# design.net
KiCad netlist of a schematic drawn in Altium Designer
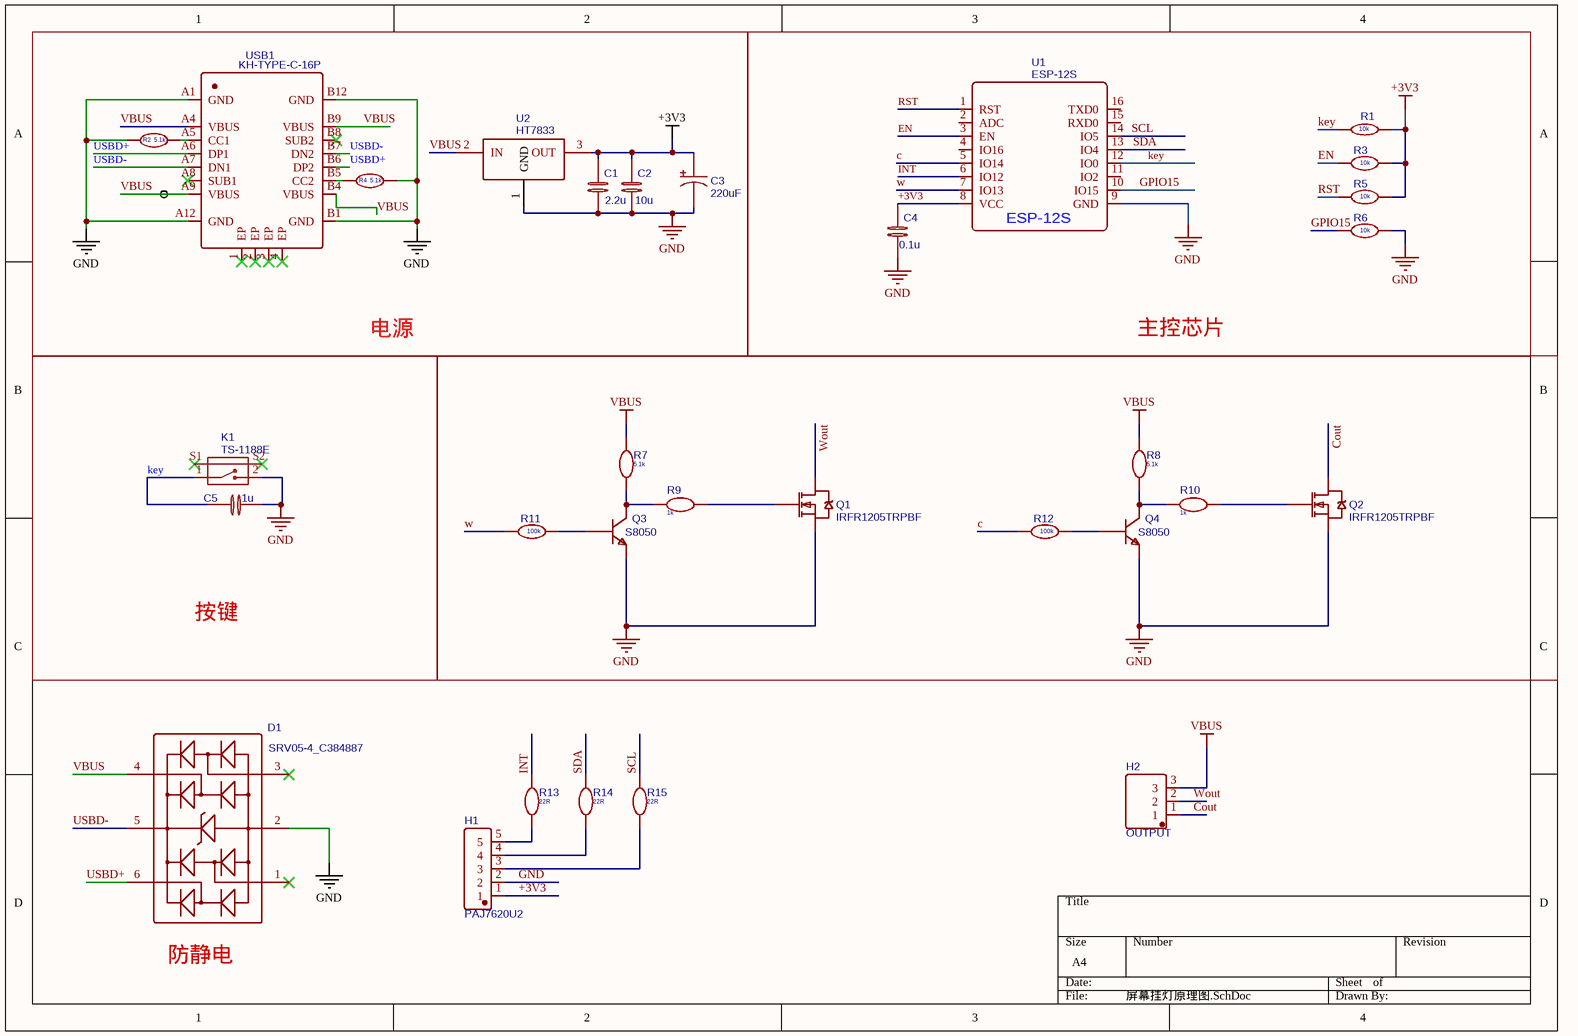
[diagram p0: 屏幕挂灯原理图.SchDoc]

(export (version "E")
  (design (tool "Eeschema 10.0.6"))
  (components
    (comp (ref "C1")
      (value "2.2u")
      (footprint "C0603")
      (fields (field (name "CONTRIBUTOR") "LCEDA_Lib"))
      (libsource (lib "altium-import") (part "root_1_2.2u_"))
    )
    (comp (ref "C2")
      (value "10u")
      (footprint "C0603")
      (fields (field (name "CONTRIBUTOR") "LCEDA_Lib"))
      (libsource (lib "altium-import") (part "root_1_10u_"))
    )
    (comp (ref "C3")
      (value "220uF")
      (footprint "CAP-SMD_BD5.0-L5.3-W5.3-FD")
      (fields
        (field (name "BOM_SUPPLIER PART") "C336271")
        (field (name "BOM_MANUFACTURER PART") "EEEFT0J221AR")
        (field (name "CONTRIBUTOR") "LCSC")
      )
      (libsource (lib "altium-import") (part "root_0_220uF_"))
    )
    (comp (ref "C4")
      (value "0.1u")
      (footprint "C0603")
      (fields (field (name "CONTRIBUTOR") "LCEDA_Lib"))
      (libsource (lib "altium-import") (part "root_1_0.1u_"))
    )
    (comp (ref "C5")
      (value "1u")
      (footprint "C0603")
      (fields (field (name "CONTRIBUTOR") "LCEDA_Lib"))
      (libsource (lib "altium-import") (part "root_2_1u_"))
    )
    (comp (ref "D1")
      (value "SRV05-4_C384887")
      (footprint "SOT-23-6_L2.9-W1.6-P0.95-LS2.8-BR")
      (fields
        (field (name "BOM_SUPPLIER PART") "C384887")
        (field (name "BOM_MANUFACTURER PART") "SRV05-4")
        (field (name "CONTRIBUTOR") "LCSC")
      )
      (libsource (lib "altium-import") (part "root_1_SRV05-4_C384887_"))
    )
    (comp (ref "H1")
      (value "PAJ7620U2")
      (footprint "HDR-TH_5P-P2.54-V-M")
      (fields
        (field (name "BOM_SUPPLIER PART") "C2932699")
        (field (name "BOM_MANUFACTURER PART") "KH-2.54PH180-1X5P-L11.5")
        (field (name "CONTRIBUTOR") "LCSC")
      )
      (libsource (lib "altium-import") (part "root_2_KH-2.54PH180-1X5P-L11.5_"))
    )
    (comp (ref "H2")
      (value "OUTPUT")
      (footprint "HDR-TH_3P-P2.54-V-M-1")
      (fields
        (field (name "BOM_SUPPLIER PART") "C168677")
        (field (name "BOM_MANUFACTURER PART") "68000-103HLF")
        (field (name "CONTRIBUTOR") "LCSC")
      )
      (libsource (lib "altium-import") (part "root_2_68000-103HLF_"))
    )
    (comp (ref "K1")
      (value "TS-1188E")
      (footprint "SMD SWITCH 7X3.6X2.7")
      (fields
        (field (name "BOM_MANUFACTURER PART") "3*6*3.5 Side press  High temperature")
        (field (name "BOM_SUPPLIER PART") "C37327")
      )
      (libsource (lib "altium-import") (part "root_0_TS-1188E_"))
    )
    (comp (ref "Q1")
      (value "IRFR1205TRPBF")
      (footprint "TO-252-2_L6.5-W6.1-P4.58-LS10.0-TR")
      (fields (field (name "BOM_SUPPLIER PART") "C81467"))
      (libsource (lib "altium-import") (part "root_0_IRFR1205TRPBF_"))
    )
    (comp (ref "Q2")
      (value "IRFR1205TRPBF")
      (footprint "TO-252-2_L6.5-W6.1-P4.58-LS10.0-TR")
      (fields (field (name "BOM_SUPPLIER PART") "C81467"))
      (libsource (lib "altium-import") (part "root_0_IRFR1205TRPBF_"))
    )
    (comp (ref "Q3")
      (value "S8050")
      (footprint "SOT-23(SOT-23-3)")
      (fields (field (name "BOM_SUPPLIER PART") "C139514") (field (name "CONTRIBUTOR") "LCSC"))
      (libsource (lib "altium-import") (part "root_2_S8050_"))
    )
    (comp (ref "Q4")
      (value "S8050")
      (footprint "SOT-23(SOT-23-3)")
      (fields (field (name "BOM_SUPPLIER PART") "C139514") (field (name "CONTRIBUTOR") "LCSC"))
      (libsource (lib "altium-import") (part "root_2_S8050_"))
    )
    (comp (ref "R1")
      (value "10k")
      (footprint "R0603")
      (fields
        (field (name "BOM_MANUFACTURER PART") "CRCW060310K0JNEA")
        (field (name "BOM_SUPPLIER PART") "C169103")
      )
      (libsource (lib "altium-import") (part "root_0_10k_"))
    )
    (comp (ref "R2")
      (value "5.1k")
      (footprint "R0603")
      (fields (field (name "CONTRIBUTOR") "LCEDA_Lib"))
      (libsource (lib "altium-import") (part "root_0_5.1k_"))
    )
    (comp (ref "R3")
      (value "10k")
      (footprint "R0603")
      (fields (field (name "CONTRIBUTOR") "LCEDA_Lib"))
      (libsource (lib "altium-import") (part "root_0_NC_"))
    )
    (comp (ref "R4")
      (value "5.1k")
      (footprint "R0603")
      (fields (field (name "CONTRIBUTOR") "LCEDA_Lib"))
      (libsource (lib "altium-import") (part "root_0_5.1k_"))
    )
    (comp (ref "R5")
      (value "10k")
      (footprint "R0603")
      (fields (field (name "CONTRIBUTOR") "LCEDA_Lib"))
      (libsource (lib "altium-import") (part "root_0_NC_"))
    )
    (comp (ref "R6")
      (value "10k")
      (footprint "R0603")
      (fields (field (name "CONTRIBUTOR") "LCEDA_Lib"))
      (libsource (lib "altium-import") (part "root_0_NC_"))
    )
    (comp (ref "R7")
      (value "5.1k")
      (footprint "R0603")
      (fields (field (name "CONTRIBUTOR") "LCEDA_Lib"))
      (libsource (lib "altium-import") (part "root_1_NC_"))
    )
    (comp (ref "R8")
      (value "5.1k")
      (footprint "R0603")
      (fields (field (name "CONTRIBUTOR") "LCEDA_Lib"))
      (libsource (lib "altium-import") (part "root_1_NC_"))
    )
    (comp (ref "R9")
      (value "1k")
      (footprint "R0603")
      (fields (field (name "CONTRIBUTOR") "LCEDA_Lib"))
      (libsource (lib "altium-import") (part "root_2_NC_"))
    )
    (comp (ref "R10")
      (value "1k")
      (footprint "R0603")
      (fields (field (name "CONTRIBUTOR") "LCEDA_Lib"))
      (libsource (lib "altium-import") (part "root_2_NC_"))
    )
    (comp (ref "R11")
      (value "100k")
      (footprint "R0603")
      (fields (field (name "CONTRIBUTOR") "LCEDA_Lib"))
      (libsource (lib "altium-import") (part "root_0_NC_"))
    )
    (comp (ref "R12")
      (value "100k")
      (footprint "R0603")
      (fields (field (name "CONTRIBUTOR") "LCEDA_Lib"))
      (libsource (lib "altium-import") (part "root_0_NC_"))
    )
    (comp (ref "R13")
      (value "22R")
      (footprint "R0603")
      (fields (field (name "CONTRIBUTOR") "LCEDA_Lib"))
      (libsource (lib "altium-import") (part "root_1_NC_"))
    )
    (comp (ref "R14")
      (value "22R")
      (footprint "R0603")
      (fields (field (name "CONTRIBUTOR") "LCEDA_Lib"))
      (libsource (lib "altium-import") (part "root_1_NC_"))
    )
    (comp (ref "R15")
      (value "22R")
      (footprint "R0603")
      (fields (field (name "CONTRIBUTOR") "LCEDA_Lib"))
      (libsource (lib "altium-import") (part "root_1_NC_"))
    )
    (comp (ref "U1")
      (value "ESP-12S")
      (footprint "WIFIM-SMD_ESP-12F-ESP8266MOD")
      (fields (field (name "BOM_SUPPLIER PART") "C82898") (field (name "CONTRIBUTOR") "HalfSweet"))
      (libsource (lib "altium-import") (part "root_0_ESP-12S_"))
    )
    (comp (ref "U2")
      (value "HT7833")
      (footprint "SOT-89_L4.5-W2.5-P1.50-LS4.2-BR")
      (fields (field (name "BOM_SUPPLIER PART") "C50936"))
      (libsource (lib "altium-import") (part "root_0_HT7833_"))
    )
    (comp (ref "USB1")
      (value "KH-TYPE-C-16P")
      (footprint "PcbLib1screen:USB-C-SMD_KH-TYPE-C-16P")
      (fields (field (name "BOM_SUPPLIER PART") "C709357") (field (name "CONTRIBUTOR") "LCSC"))
      (libsource (lib "altium-import") (part "root_0_KH-TYPE-C-16P_"))
    )
  )
  (nets
    (net (code "1") (name "+3V3") (class "Default")
      (node (ref "C1") (pin "2") (pinfunction "2_2") (pintype "passive"))
      (node (ref "C2") (pin "2") (pinfunction "2_2") (pintype "passive"))
      (node (ref "C3") (pin "1") (pinfunction "1_1") (pintype "passive"))
      (node (ref "C4") (pin "2") (pinfunction "2_2") (pintype "passive"))
      (node (ref "H1") (pin "1") (pinfunction "1_1") (pintype "passive"))
      (node (ref "R1") (pin "1") (pinfunction "1_1") (pintype "passive"))
      (node (ref "R3") (pin "2") (pinfunction "2_2") (pintype "passive"))
      (node (ref "R5") (pin "2") (pinfunction "2_2") (pintype "passive"))
      (node (ref "U1") (pin "8") (pinfunction "VCC_8") (pintype "passive"))
      (node (ref "U2") (pin "3") (pinfunction "OUT_3") (pintype "passive"))
    )
    (net (code "2") (name "/Cout") (class "Default")
      (node (ref "H2") (pin "1") (pinfunction "1_1") (pintype "passive"))
      (node (ref "Q2") (pin "4") (pinfunction "D_4") (pintype "passive"))
    )
    (net (code "3") (name "/EN") (class "Default")
      (node (ref "R3") (pin "1") (pinfunction "1_1") (pintype "passive"))
      (node (ref "U1") (pin "3") (pinfunction "EN_3") (pintype "passive"))
    )
    (net (code "4") (name "/GPIO15") (class "Default")
      (node (ref "R6") (pin "1") (pinfunction "1_1") (pintype "passive"))
      (node (ref "U1") (pin "10") (pinfunction "IO15_10") (pintype "passive"))
    )
    (net (code "5") (name "/INT") (class "Default")
      (node (ref "R13") (pin "2") (pinfunction "2_2") (pintype "passive"))
      (node (ref "U1") (pin "6") (pinfunction "IO12_6") (pintype "passive"))
    )
    (net (code "6") (name "/RST") (class "Default")
      (node (ref "R5") (pin "1") (pinfunction "1_1") (pintype "passive"))
      (node (ref "U1") (pin "1") (pinfunction "RST_1") (pintype "passive"))
    )
    (net (code "7") (name "/SCL") (class "Default")
      (node (ref "R15") (pin "2") (pinfunction "2_2") (pintype "passive"))
      (node (ref "U1") (pin "14") (pinfunction "IO5_14") (pintype "passive"))
    )
    (net (code "8") (name "/SDA") (class "Default")
      (node (ref "R14") (pin "2") (pinfunction "2_2") (pintype "passive"))
      (node (ref "U1") (pin "13") (pinfunction "IO4_13") (pintype "passive"))
    )
    (net (code "9") (name "/USBD+") (class "Default")
      (node (ref "D1") (pin "6") (pinfunction "IO2_6") (pintype "passive"))
      (node (ref "USB1") (pin "A6") (pinfunction "DP1_A6") (pintype "passive"))
      (node (ref "USB1") (pin "B6") (pinfunction "DP2_B6") (pintype "passive"))
    )
    (net (code "10") (name "/USBD-") (class "Default")
      (node (ref "D1") (pin "5") (pinfunction "VCC_5") (pintype "passive"))
      (node (ref "USB1") (pin "A7") (pinfunction "DN1_A7") (pintype "passive"))
      (node (ref "USB1") (pin "B7") (pinfunction "DN2_B7") (pintype "passive"))
    )
    (net (code "11") (name "/Wout") (class "Default")
      (node (ref "H2") (pin "2") (pinfunction "2_2") (pintype "passive"))
      (node (ref "Q1") (pin "4") (pinfunction "D_4") (pintype "passive"))
    )
    (net (code "12") (name "/c") (class "Default")
      (node (ref "R12") (pin "1") (pinfunction "1_1") (pintype "passive"))
      (node (ref "U1") (pin "5") (pinfunction "IO14_5") (pintype "passive"))
    )
    (net (code "13") (name "/key") (class "Default")
      (node (ref "C5") (pin "2") (pinfunction "2_2") (pintype "passive"))
      (node (ref "K1") (pin "1") (pinfunction "1_1") (pintype "passive"))
      (node (ref "R1") (pin "2") (pinfunction "2_2") (pintype "passive"))
      (node (ref "U1") (pin "12") (pinfunction "IO0_12") (pintype "passive"))
    )
    (net (code "14") (name "/w") (class "Default")
      (node (ref "R11") (pin "1") (pinfunction "1_1") (pintype "passive"))
      (node (ref "U1") (pin "7") (pinfunction "IO13_7") (pintype "passive"))
    )
    (net (code "15") (name "GND") (class "Default")
      (node (ref "C1") (pin "1") (pinfunction "1_1") (pintype "passive"))
      (node (ref "C2") (pin "1") (pinfunction "1_1") (pintype "passive"))
      (node (ref "C3") (pin "2") (pinfunction "2_2") (pintype "passive"))
      (node (ref "C4") (pin "1") (pinfunction "1_1") (pintype "passive"))
      (node (ref "C5") (pin "1") (pinfunction "1_1") (pintype "passive"))
      (node (ref "D1") (pin "2") (pinfunction "GND_2") (pintype "passive"))
      (node (ref "H1") (pin "2") (pinfunction "2_2") (pintype "passive"))
      (node (ref "K1") (pin "2") (pinfunction "2_2") (pintype "passive"))
      (node (ref "Q1") (pin "3") (pinfunction "S_3") (pintype "passive"))
      (node (ref "Q2") (pin "3") (pinfunction "S_3") (pintype "passive"))
      (node (ref "Q3") (pin "2") (pinfunction "E_2") (pintype "passive"))
      (node (ref "Q4") (pin "2") (pinfunction "E_2") (pintype "passive"))
      (node (ref "R2") (pin "1") (pinfunction "1_1") (pintype "passive"))
      (node (ref "R4") (pin "2") (pinfunction "2_2") (pintype "passive"))
      (node (ref "R6") (pin "2") (pinfunction "2_2") (pintype "passive"))
      (node (ref "U1") (pin "9") (pinfunction "GND_9") (pintype "passive"))
      (node (ref "U2") (pin "1") (pinfunction "GND_1") (pintype "passive"))
      (node (ref "USB1") (pin "A1") (pinfunction "GND_A1") (pintype "passive"))
      (node (ref "USB1") (pin "A12") (pinfunction "GND_A12") (pintype "passive"))
      (node (ref "USB1") (pin "B1") (pinfunction "GND_B1") (pintype "passive"))
      (node (ref "USB1") (pin "B12") (pinfunction "GND_B12") (pintype "passive"))
    )
    (net (code "16") (name "Net-(H1-Pad3)") (class "Default")
      (node (ref "H1") (pin "3") (pinfunction "3_3") (pintype "passive"))
      (node (ref "R15") (pin "1") (pinfunction "1_1") (pintype "passive"))
    )
    (net (code "17") (name "Net-(H1-Pad4)") (class "Default")
      (node (ref "H1") (pin "4") (pinfunction "4_4") (pintype "passive"))
      (node (ref "R14") (pin "1") (pinfunction "1_1") (pintype "passive"))
    )
    (net (code "18") (name "Net-(H1-Pad5)") (class "Default")
      (node (ref "H1") (pin "5") (pinfunction "5_5") (pintype "passive"))
      (node (ref "R13") (pin "1") (pinfunction "1_1") (pintype "passive"))
    )
    (net (code "19") (name "Net-(Q1-G)") (class "Default")
      (node (ref "Q1") (pin "1") (pinfunction "G_1") (pintype "passive"))
      (node (ref "R9") (pin "1") (pinfunction "1_1") (pintype "passive"))
    )
    (net (code "20") (name "Net-(Q2-G)") (class "Default")
      (node (ref "Q2") (pin "1") (pinfunction "G_1") (pintype "passive"))
      (node (ref "R10") (pin "1") (pinfunction "1_1") (pintype "passive"))
    )
    (net (code "21") (name "Net-(Q3-B)") (class "Default")
      (node (ref "Q3") (pin "1") (pinfunction "B_1") (pintype "passive"))
      (node (ref "R11") (pin "2") (pinfunction "2_2") (pintype "passive"))
    )
    (net (code "22") (name "Net-(Q3-C)") (class "Default")
      (node (ref "Q3") (pin "3") (pinfunction "C_3") (pintype "passive"))
      (node (ref "R7") (pin "1") (pinfunction "1_1") (pintype "passive"))
      (node (ref "R9") (pin "2") (pinfunction "2_2") (pintype "passive"))
    )
    (net (code "23") (name "Net-(Q4-B)") (class "Default")
      (node (ref "Q4") (pin "1") (pinfunction "B_1") (pintype "passive"))
      (node (ref "R12") (pin "2") (pinfunction "2_2") (pintype "passive"))
    )
    (net (code "24") (name "Net-(Q4-C)") (class "Default")
      (node (ref "Q4") (pin "3") (pinfunction "C_3") (pintype "passive"))
      (node (ref "R10") (pin "2") (pinfunction "2_2") (pintype "passive"))
      (node (ref "R8") (pin "1") (pinfunction "1_1") (pintype "passive"))
    )
    (net (code "25") (name "Net-(USB1-CC1)") (class "Default")
      (node (ref "R2") (pin "2") (pinfunction "2_2") (pintype "passive"))
      (node (ref "USB1") (pin "A5") (pinfunction "CC1_A5") (pintype "passive"))
    )
    (net (code "26") (name "Net-(USB1-CC2)") (class "Default")
      (node (ref "R4") (pin "1") (pinfunction "1_1") (pintype "passive"))
      (node (ref "USB1") (pin "B5") (pinfunction "CC2_B5") (pintype "passive"))
    )
    (net (code "27") (name "VBUS") (class "Default")
      (node (ref "D1") (pin "4") (pinfunction "IO4_4") (pintype "passive"))
      (node (ref "H2") (pin "3") (pinfunction "3_3") (pintype "passive"))
      (node (ref "R7") (pin "2") (pinfunction "2_2") (pintype "passive"))
      (node (ref "R8") (pin "2") (pinfunction "2_2") (pintype "passive"))
      (node (ref "U2") (pin "2") (pinfunction "IN_2") (pintype "passive"))
      (node (ref "USB1") (pin "A4") (pinfunction "VBUS_A4") (pintype "passive"))
      (node (ref "USB1") (pin "A9") (pinfunction "VBUS_A9") (pintype "passive"))
      (node (ref "USB1") (pin "B4") (pinfunction "VBUS_B4") (pintype "passive"))
      (node (ref "USB1") (pin "B9") (pinfunction "VBUS_B9") (pintype "passive"))
    )
    (net (code "28") (name "unconnected-(D1-IO1-Pad1)") (class "Default")
      (node (ref "D1") (pin "1") (pinfunction "IO1_1") (pintype "passive+no_connect"))
    )
    (net (code "29") (name "unconnected-(D1-IO3-Pad3)") (class "Default")
      (node (ref "D1") (pin "3") (pinfunction "IO3_3") (pintype "passive+no_connect"))
    )
    (net (code "30") (name "unconnected-(K1-PadS1)") (class "Default")
      (node (ref "K1") (pin "S1") (pinfunction "S1_S1") (pintype "passive+no_connect"))
    )
    (net (code "31") (name "unconnected-(K1-PadS2)") (class "Default")
      (node (ref "K1") (pin "S2") (pinfunction "S2_S2") (pintype "passive+no_connect"))
    )
    (net (code "32") (name "unconnected-(U1-ADC-Pad2)") (class "Default")
      (node (ref "U1") (pin "2") (pinfunction "ADC_2") (pintype "passive"))
    )
    (net (code "33") (name "unconnected-(U1-IO2-Pad11)") (class "Default")
      (node (ref "U1") (pin "11") (pinfunction "IO2_11") (pintype "passive"))
    )
    (net (code "34") (name "unconnected-(U1-IO16-Pad4)") (class "Default")
      (node (ref "U1") (pin "4") (pinfunction "IO16_4") (pintype "passive"))
    )
    (net (code "35") (name "unconnected-(U1-RXD0-Pad15)") (class "Default")
      (node (ref "U1") (pin "15") (pinfunction "RXD0_15") (pintype "passive"))
    )
    (net (code "36") (name "unconnected-(U1-TXD0-Pad16)") (class "Default")
      (node (ref "U1") (pin "16") (pinfunction "TXD0_16") (pintype "passive"))
    )
    (net (code "37") (name "unconnected-(USB1-EP-Pad1)") (class "Default")
      (node (ref "USB1") (pin "1") (pinfunction "EP_1") (pintype "passive+no_connect"))
    )
    (net (code "38") (name "unconnected-(USB1-EP-Pad2)") (class "Default")
      (node (ref "USB1") (pin "2") (pinfunction "EP_2") (pintype "passive+no_connect"))
    )
    (net (code "39") (name "unconnected-(USB1-EP-Pad3)") (class "Default")
      (node (ref "USB1") (pin "3") (pinfunction "EP_3") (pintype "passive+no_connect"))
    )
    (net (code "40") (name "unconnected-(USB1-EP-Pad4)") (class "Default")
      (node (ref "USB1") (pin "4") (pinfunction "EP_4") (pintype "passive+no_connect"))
    )
    (net (code "41") (name "unconnected-(USB1-SUB1-PadA8)") (class "Default")
      (node (ref "USB1") (pin "A8") (pinfunction "SUB1_A8") (pintype "passive+no_connect"))
    )
    (net (code "42") (name "unconnected-(USB1-SUB2-PadB8)") (class "Default")
      (node (ref "USB1") (pin "B8") (pinfunction "SUB2_B8") (pintype "passive+no_connect"))
    )
  )
)
